# S7CAS-PLEIADES-CARTE-MERE_Pxx_ARBRE_CAP_.net
KiCad netlist of a schematic drawn in Altium Designer
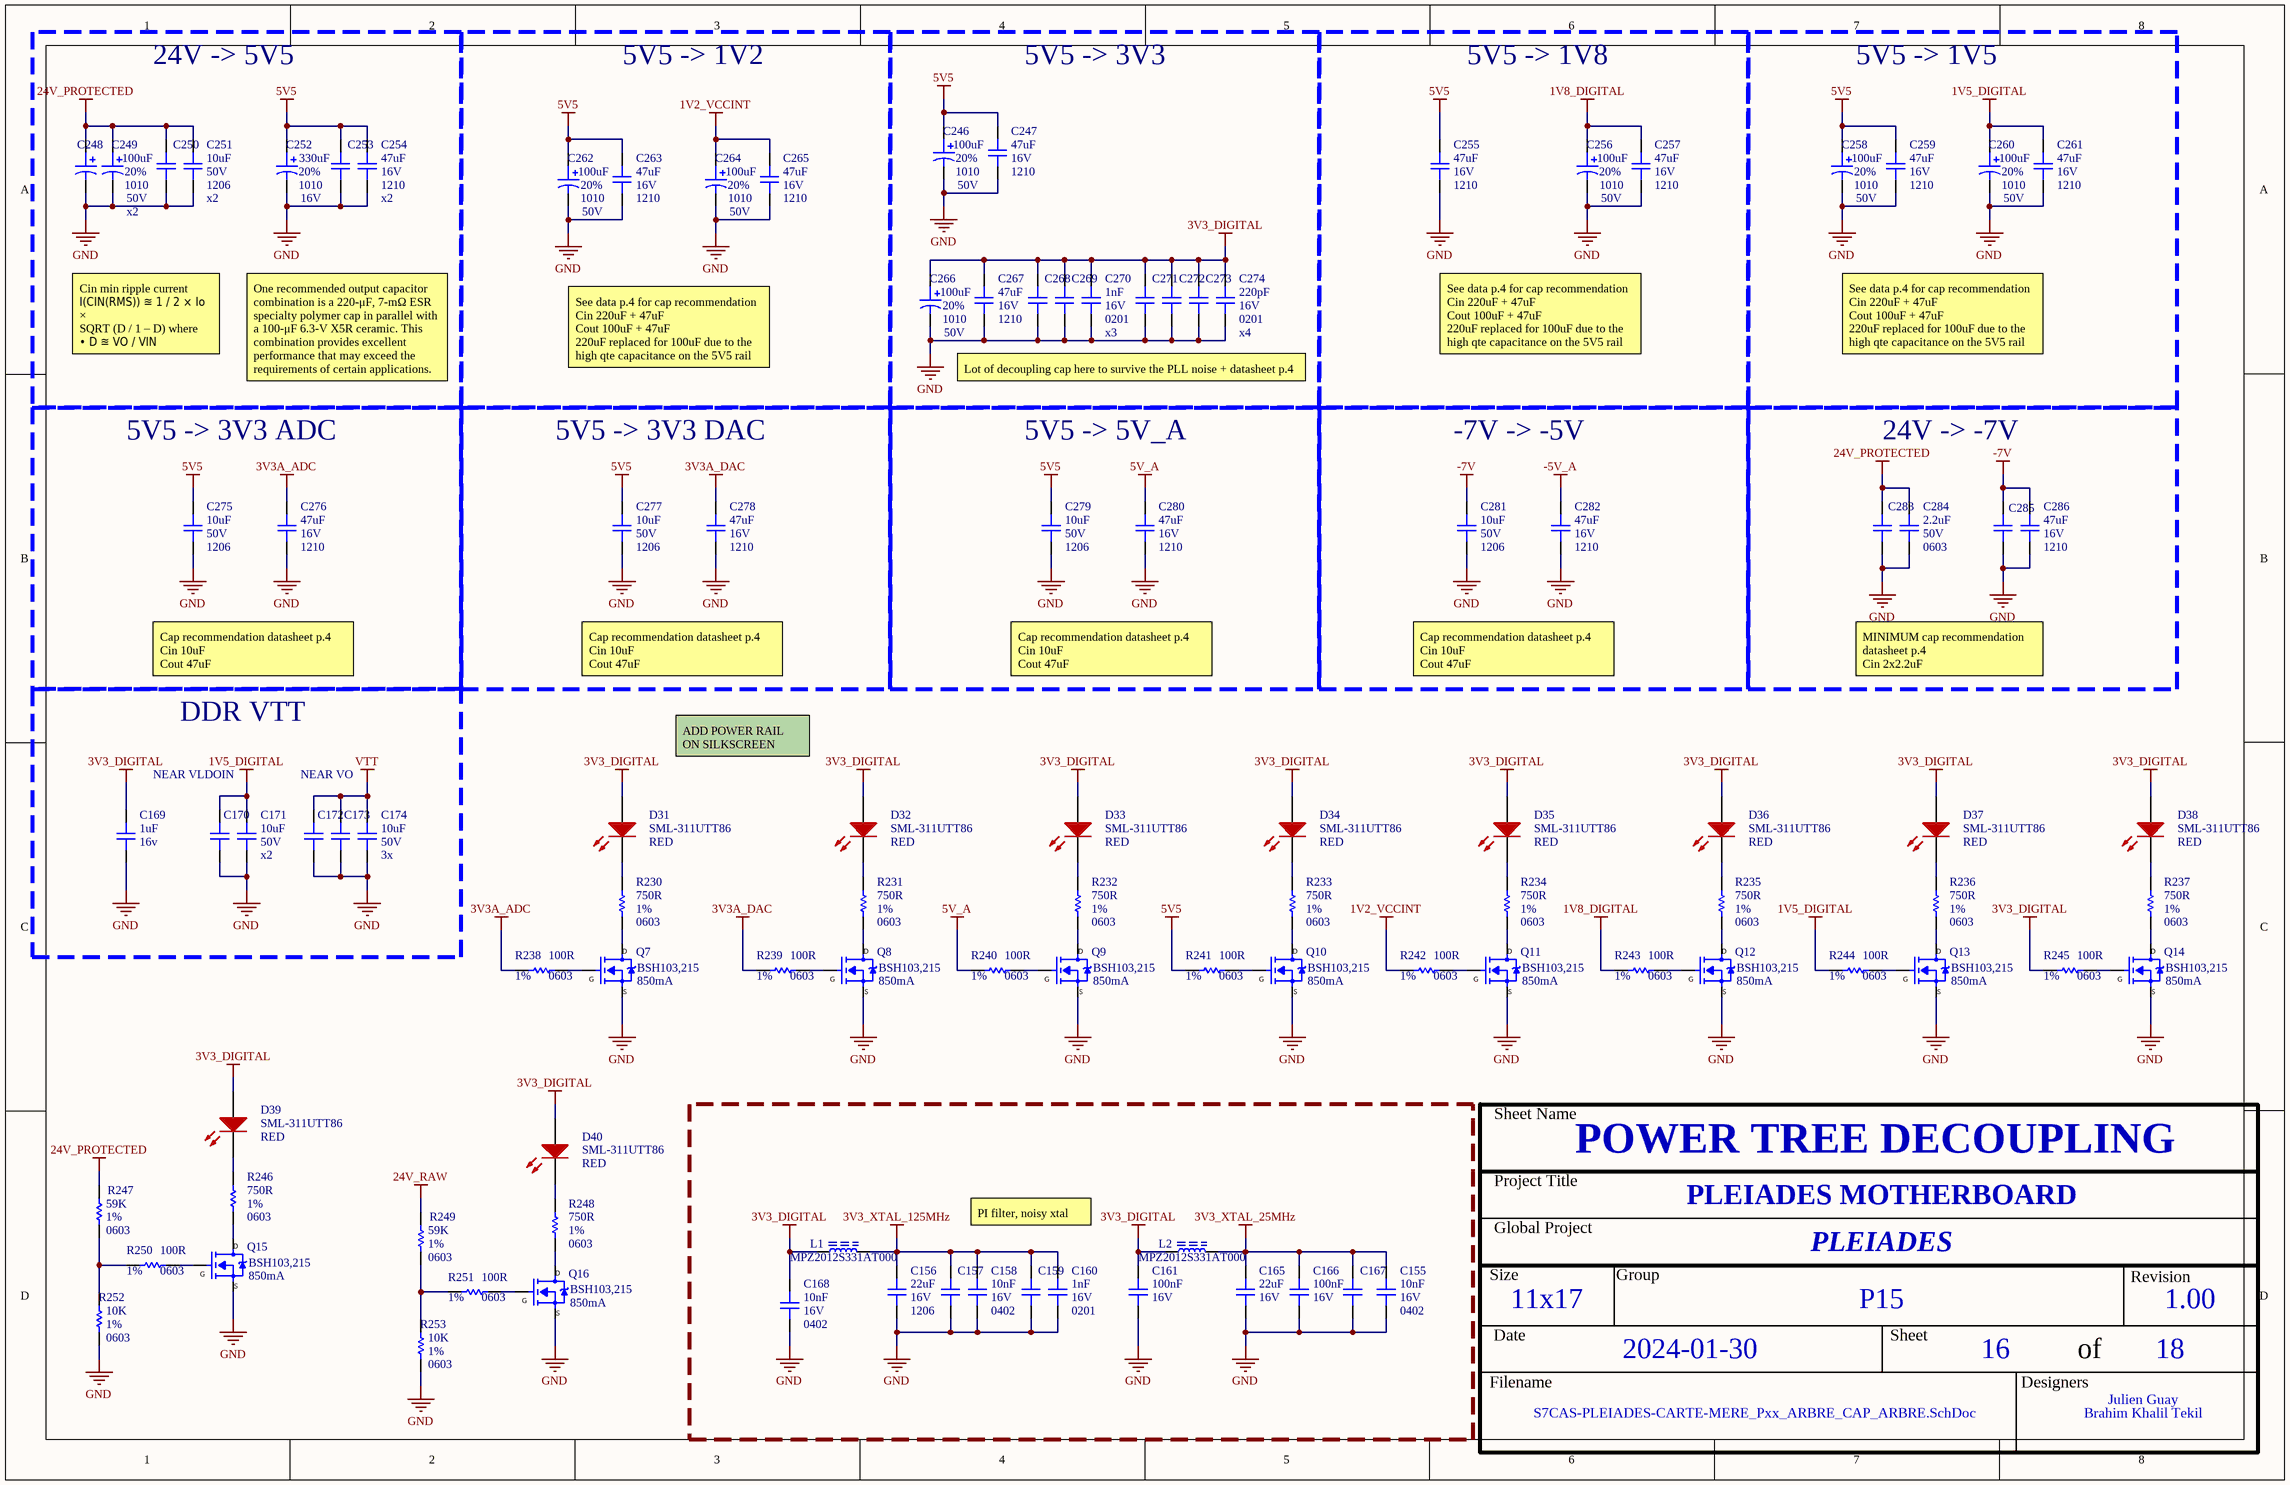
[diagram p0: S7CAS-PLEIADES-CARTE-MERE_Pxx_ARBRE_CAP_ARBRE.SchDoc]

(export (version "E")
  (design (tool "Eeschema 10.0.6"))
  (components
    (comp (ref "C155")
      (value "10nF")
      (footprint "CAP_0402")
      (description "CAP - 0402")
      (fields
        (field (name "VOLTAGE") "16V")
        (field (name "PACKAGE") "0402")
        (field (name "CREATEDBY") "Jonathan Bouchard")
      )
      (libsource (lib "S7CAS_LIB2023") (part "CAP - 0402"))
    )
    (comp (ref "C156")
      (value "22uF")
      (footprint "CAP_1206")
      (description "CAP - 1206")
      (fields
        (field (name "VOLTAGE") "16V")
        (field (name "PACKAGE") "1206")
        (field (name "CREATEDBY") "Jonathan Bouchard")
      )
      (libsource (lib "S7CAS_LIB2023") (part "CAP - 1206"))
    )
    (comp (ref "C157")
      (value "CAP - 0402")
      (footprint "CAP_0402")
      (fields (field (name "VOLTAGE") "16V") (field (name "CREATEDBY") "Jonathan Bouchard"))
      (libsource (lib "S7CAS_LIB2023") (part "CAP - 0402"))
    )
    (comp (ref "C158")
      (value "10nF")
      (footprint "CAP_0402")
      (description "CAP - 0402")
      (fields
        (field (name "VOLTAGE") "16V")
        (field (name "PACKAGE") "0402")
        (field (name "CREATEDBY") "Jonathan Bouchard")
      )
      (libsource (lib "S7CAS_LIB2023") (part "CAP - 0402"))
    )
    (comp (ref "C159")
      (value "CAP - 0201")
      (footprint "CAP_0201")
      (fields (field (name "VOLTAGE") "16V") (field (name "CREATEDBY") "Jonathan Bouchard"))
      (libsource (lib "S7CAS_LIB2023") (part "CAP - 0201"))
    )
    (comp (ref "C160")
      (value "1nF")
      (footprint "CAP_0201")
      (description "CAP - 0201")
      (fields
        (field (name "VOLTAGE") "16V")
        (field (name "PACKAGE") "0201")
        (field (name "CREATEDBY") "Jonathan Bouchard")
      )
      (libsource (lib "S7CAS_LIB2023") (part "CAP - 0201"))
    )
    (comp (ref "C161")
      (value "100nF")
      (footprint "CAP_0603")
      (description "CAP - 0603")
      (fields (field (name "VOLTAGE") "16V") (field (name "CREATEDBY") "Jonathan Bouchard"))
      (libsource (lib "S7CAS_LIB2023") (part "CAP - 0603"))
    )
    (comp (ref "C165")
      (value "22uF")
      (footprint "CAP_1206")
      (description "CAP - 1206")
      (fields (field (name "VOLTAGE") "16V") (field (name "CREATEDBY") "Jonathan Bouchard"))
      (libsource (lib "S7CAS_LIB2023") (part "CAP - 1206"))
    )
    (comp (ref "C166")
      (value "100nF")
      (footprint "CAP_0603")
      (description "CAP - 0603")
      (fields (field (name "VOLTAGE") "16V") (field (name "CREATEDBY") "Jonathan Bouchard"))
      (libsource (lib "S7CAS_LIB2023") (part "CAP - 0603"))
    )
    (comp (ref "C167")
      (value "CAP - 0402")
      (footprint "CAP_0402")
      (fields (field (name "VOLTAGE") "16V") (field (name "CREATEDBY") "Jonathan Bouchard"))
      (libsource (lib "S7CAS_LIB2023") (part "CAP - 0402"))
    )
    (comp (ref "C168")
      (value "10nF")
      (footprint "CAP_0402")
      (description "CAP - 0402")
      (fields
        (field (name "VOLTAGE") "16V")
        (field (name "PACKAGE") "0402")
        (field (name "CREATEDBY") "Jonathan Bouchard")
      )
      (libsource (lib "S7CAS_LIB2023") (part "CAP - 0402"))
    )
    (comp (ref "C169")
      (value "1uF")
      (footprint "CAP_0603")
      (description "CAP - 0603")
      (fields (field (name "VOLTAGE") "16v") (field (name "CREATEDBY") "Jonathan Bouchard"))
      (libsource (lib "S7CAS_LIB2023") (part "CAP - 0603"))
    )
    (comp (ref "C170")
      (value "CAP - 0805")
      (footprint "CAP_0805")
      (fields (field (name "VOLTAGE") "50V") (field (name "CREATEDBY") "Jonathan Bouchard"))
      (libsource (lib "S7CAS_LIB2023") (part "CAP - 0805"))
    )
    (comp (ref "C171")
      (value "10uF")
      (footprint "CAP_0805")
      (description "CAP - 0805")
      (fields (field (name "VOLTAGE") "50V") (field (name "CREATEDBY") "Jonathan Bouchard"))
      (libsource (lib "S7CAS_LIB2023") (part "CAP - 0805"))
    )
    (comp (ref "C172")
      (value "CAP - 0805")
      (footprint "CAP_0805")
      (fields (field (name "VOLTAGE") "50V") (field (name "CREATEDBY") "Jonathan Bouchard"))
      (libsource (lib "S7CAS_LIB2023") (part "CAP - 0805"))
    )
    (comp (ref "C173")
      (value "CAP - 0805")
      (footprint "CAP_0805")
      (fields (field (name "VOLTAGE") "50V") (field (name "CREATEDBY") "Jonathan Bouchard"))
      (libsource (lib "S7CAS_LIB2023") (part "CAP - 0805"))
    )
    (comp (ref "C174")
      (value "10uF")
      (footprint "CAP_0805")
      (description "CAP - 0805")
      (fields (field (name "VOLTAGE") "50V") (field (name "CREATEDBY") "Jonathan Bouchard"))
      (libsource (lib "S7CAS_LIB2023") (part "CAP - 0805"))
    )
    (comp (ref "C246")
      (value "100uF")
      (footprint "CAP_ALU_1010_vishay")
      (description "CAP - ALU 100uF 20% 50V - 1010")
      (fields
        (field (name "MFG") "Vishay Dale")
        (field (name "MFG PART NUMBER") "MAL215099101E3")
        (field (name "VOLTAGE") "50V")
        (field (name "PACKAGE") "1010")
        (field (name "PRECISION") "20%")
        (field (name "CREATEDBY") "Jonathan Bouchard")
      )
      (libsource (lib "S7CAS_LIB2023") (part "CAP_ALU_MAL215099101E3"))
    )
    (comp (ref "C247")
      (value "47uF")
      (footprint "CAP_1210")
      (description "CAP - 1210")
      (fields
        (field (name "VOLTAGE") "16V")
        (field (name "PACKAGE") "1210")
        (field (name "CREATEDBY") "Jonathan Bouchard")
      )
      (libsource (lib "S7CAS_LIB2023") (part "CAP - 1210"))
    )
    (comp (ref "C248")
      (value "MAL215099101E3")
      (footprint "CAP_ALU_1010_vishay")
      (description "CAP - ALU 100uF 20% 50V - 1010")
      (fields (field (name "MFG") "Vishay Dale") (field (name "CREATEDBY") "Jonathan Bouchard"))
      (libsource (lib "S7CAS_LIB2023") (part "CAP_ALU_MAL215099101E3"))
    )
    (comp (ref "C249")
      (value "100uF")
      (footprint "CAP_ALU_1010_vishay")
      (description "CAP - ALU 100uF 20% 50V - 1010")
      (fields
        (field (name "MFG") "Vishay Dale")
        (field (name "MFG PART NUMBER") "MAL215099101E3")
        (field (name "VOLTAGE") "50V")
        (field (name "PACKAGE") "1010")
        (field (name "PRECISION") "20%")
        (field (name "CREATEDBY") "Jonathan Bouchard")
      )
      (libsource (lib "S7CAS_LIB2023") (part "CAP_ALU_MAL215099101E3"))
    )
    (comp (ref "C250")
      (value "CAP - 1206")
      (footprint "CAP_1206")
      (fields (field (name "VOLTAGE") "50V") (field (name "CREATEDBY") "Jonathan Bouchard"))
      (libsource (lib "S7CAS_LIB2023") (part "CAP - 1206"))
    )
    (comp (ref "C251")
      (value "10uF")
      (footprint "CAP_1206")
      (description "CAP - 1206")
      (fields
        (field (name "VOLTAGE") "50V")
        (field (name "PACKAGE") "1206")
        (field (name "CREATEDBY") "Jonathan Bouchard")
      )
      (libsource (lib "S7CAS_LIB2023") (part "CAP - 1206"))
    )
    (comp (ref "C252")
      (value "330uF")
      (footprint "CAP_ALU_1010_vishay")
      (description "CAP - ALU 330uF 20% 16V - 1010")
      (fields
        (field (name "MFG") "Vishay Dale")
        (field (name "MFG PART NUMBER") "MAL214699501E3")
        (field (name "VOLTAGE") "16V")
        (field (name "PACKAGE") "1010")
        (field (name "PRECISION") "20%")
        (field (name "CREATEDBY") "Jonathan Bouchard")
      )
      (libsource (lib "S7CAS_LIB2023") (part "CAP_ALU_MAL214699501E3"))
    )
    (comp (ref "C253")
      (value "CAP - 1210")
      (footprint "CAP_1210")
      (fields (field (name "VOLTAGE") "16V") (field (name "CREATEDBY") "Jonathan Bouchard"))
      (libsource (lib "S7CAS_LIB2023") (part "CAP - 1210"))
    )
    (comp (ref "C254")
      (value "47uF")
      (footprint "CAP_1210")
      (description "CAP - 1210")
      (fields
        (field (name "VOLTAGE") "16V")
        (field (name "PACKAGE") "1210")
        (field (name "CREATEDBY") "Jonathan Bouchard")
      )
      (libsource (lib "S7CAS_LIB2023") (part "CAP - 1210"))
    )
    (comp (ref "C255")
      (value "47uF")
      (footprint "CAP_1210")
      (description "CAP - 1210")
      (fields
        (field (name "VOLTAGE") "16V")
        (field (name "PACKAGE") "1210")
        (field (name "CREATEDBY") "Jonathan Bouchard")
      )
      (libsource (lib "S7CAS_LIB2023") (part "CAP - 1210"))
    )
    (comp (ref "C256")
      (value "100uF")
      (footprint "CAP_ALU_1010_vishay")
      (description "CAP - ALU 100uF 20% 50V - 1010")
      (fields
        (field (name "MFG") "Vishay Dale")
        (field (name "MFG PART NUMBER") "MAL215099101E3")
        (field (name "VOLTAGE") "50V")
        (field (name "PACKAGE") "1010")
        (field (name "PRECISION") "20%")
        (field (name "CREATEDBY") "Jonathan Bouchard")
      )
      (libsource (lib "S7CAS_LIB2023") (part "CAP_ALU_MAL215099101E3"))
    )
    (comp (ref "C257")
      (value "47uF")
      (footprint "CAP_1210")
      (description "CAP - 1210")
      (fields
        (field (name "VOLTAGE") "16V")
        (field (name "PACKAGE") "1210")
        (field (name "CREATEDBY") "Jonathan Bouchard")
      )
      (libsource (lib "S7CAS_LIB2023") (part "CAP - 1210"))
    )
    (comp (ref "C258")
      (value "100uF")
      (footprint "CAP_ALU_1010_vishay")
      (description "CAP - ALU 100uF 20% 50V - 1010")
      (fields
        (field (name "MFG") "Vishay Dale")
        (field (name "MFG PART NUMBER") "MAL215099101E3")
        (field (name "VOLTAGE") "50V")
        (field (name "PACKAGE") "1010")
        (field (name "PRECISION") "20%")
        (field (name "CREATEDBY") "Jonathan Bouchard")
      )
      (libsource (lib "S7CAS_LIB2023") (part "CAP_ALU_MAL215099101E3"))
    )
    (comp (ref "C259")
      (value "47uF")
      (footprint "CAP_1210")
      (description "CAP - 1210")
      (fields
        (field (name "VOLTAGE") "16V")
        (field (name "PACKAGE") "1210")
        (field (name "CREATEDBY") "Jonathan Bouchard")
      )
      (libsource (lib "S7CAS_LIB2023") (part "CAP - 1210"))
    )
    (comp (ref "C260")
      (value "100uF")
      (footprint "CAP_ALU_1010_vishay")
      (description "CAP - ALU 100uF 20% 50V - 1010")
      (fields
        (field (name "MFG") "Vishay Dale")
        (field (name "MFG PART NUMBER") "MAL215099101E3")
        (field (name "VOLTAGE") "50V")
        (field (name "PACKAGE") "1010")
        (field (name "PRECISION") "20%")
        (field (name "CREATEDBY") "Jonathan Bouchard")
      )
      (libsource (lib "S7CAS_LIB2023") (part "CAP_ALU_MAL215099101E3"))
    )
    (comp (ref "C261")
      (value "47uF")
      (footprint "CAP_1210")
      (description "CAP - 1210")
      (fields
        (field (name "VOLTAGE") "16V")
        (field (name "PACKAGE") "1210")
        (field (name "CREATEDBY") "Jonathan Bouchard")
      )
      (libsource (lib "S7CAS_LIB2023") (part "CAP - 1210"))
    )
    (comp (ref "C262")
      (value "100uF")
      (footprint "CAP_ALU_1010_vishay")
      (description "CAP - ALU 100uF 20% 50V - 1010")
      (fields
        (field (name "MFG") "Vishay Dale")
        (field (name "MFG PART NUMBER") "MAL215099101E3")
        (field (name "VOLTAGE") "50V")
        (field (name "PACKAGE") "1010")
        (field (name "PRECISION") "20%")
        (field (name "CREATEDBY") "Jonathan Bouchard")
      )
      (libsource (lib "S7CAS_LIB2023") (part "CAP_ALU_MAL215099101E3"))
    )
    (comp (ref "C263")
      (value "47uF")
      (footprint "CAP_1210")
      (description "CAP - 1210")
      (fields
        (field (name "VOLTAGE") "16V")
        (field (name "PACKAGE") "1210")
        (field (name "CREATEDBY") "Jonathan Bouchard")
      )
      (libsource (lib "S7CAS_LIB2023") (part "CAP - 1210"))
    )
    (comp (ref "C264")
      (value "100uF")
      (footprint "CAP_ALU_1010_vishay")
      (description "CAP - ALU 100uF 20% 50V - 1010")
      (fields
        (field (name "MFG") "Vishay Dale")
        (field (name "MFG PART NUMBER") "MAL215099101E3")
        (field (name "VOLTAGE") "50V")
        (field (name "PACKAGE") "1010")
        (field (name "PRECISION") "20%")
        (field (name "CREATEDBY") "Jonathan Bouchard")
      )
      (libsource (lib "S7CAS_LIB2023") (part "CAP_ALU_MAL215099101E3"))
    )
    (comp (ref "C265")
      (value "47uF")
      (footprint "CAP_1210")
      (description "CAP - 1210")
      (fields
        (field (name "VOLTAGE") "16V")
        (field (name "PACKAGE") "1210")
        (field (name "CREATEDBY") "Jonathan Bouchard")
      )
      (libsource (lib "S7CAS_LIB2023") (part "CAP - 1210"))
    )
    (comp (ref "C266")
      (value "100uF")
      (footprint "CAP_ALU_1010_vishay")
      (description "CAP - ALU 100uF 20% 50V - 1010")
      (fields
        (field (name "MFG") "Vishay Dale")
        (field (name "MFG PART NUMBER") "MAL215099101E3")
        (field (name "VOLTAGE") "50V")
        (field (name "PACKAGE") "1010")
        (field (name "PRECISION") "20%")
        (field (name "CREATEDBY") "Jonathan Bouchard")
      )
      (libsource (lib "S7CAS_LIB2023") (part "CAP_ALU_MAL215099101E3"))
    )
    (comp (ref "C267")
      (value "47uF")
      (footprint "CAP_1210")
      (description "CAP - 1210")
      (fields
        (field (name "VOLTAGE") "16V")
        (field (name "PACKAGE") "1210")
        (field (name "CREATEDBY") "Jonathan Bouchard")
      )
      (libsource (lib "S7CAS_LIB2023") (part "CAP - 1210"))
    )
    (comp (ref "C268")
      (value "CAP - 0201")
      (footprint "CAP_0201")
      (fields (field (name "VOLTAGE") "16V") (field (name "CREATEDBY") "Jonathan Bouchard"))
      (libsource (lib "S7CAS_LIB2023") (part "CAP - 0201"))
    )
    (comp (ref "C269")
      (value "CAP - 0201")
      (footprint "CAP_0201")
      (fields (field (name "VOLTAGE") "16V") (field (name "CREATEDBY") "Jonathan Bouchard"))
      (libsource (lib "S7CAS_LIB2023") (part "CAP - 0201"))
    )
    (comp (ref "C270")
      (value "1nF")
      (footprint "CAP_0201")
      (description "CAP - 0201")
      (fields
        (field (name "VOLTAGE") "16V")
        (field (name "PACKAGE") "0201")
        (field (name "CREATEDBY") "Jonathan Bouchard")
      )
      (libsource (lib "S7CAS_LIB2023") (part "CAP - 0201"))
    )
    (comp (ref "C271")
      (value "CAP - 0201")
      (footprint "CAP_0201")
      (fields (field (name "VOLTAGE") "16V") (field (name "CREATEDBY") "Jonathan Bouchard"))
      (libsource (lib "S7CAS_LIB2023") (part "CAP - 0201"))
    )
    (comp (ref "C272")
      (value "CAP - 0201")
      (footprint "CAP_0201")
      (fields (field (name "VOLTAGE") "16V") (field (name "CREATEDBY") "Jonathan Bouchard"))
      (libsource (lib "S7CAS_LIB2023") (part "CAP - 0201"))
    )
    (comp (ref "C273")
      (value "CAP - 0201")
      (footprint "CAP_0201")
      (fields (field (name "VOLTAGE") "16V") (field (name "CREATEDBY") "Jonathan Bouchard"))
      (libsource (lib "S7CAS_LIB2023") (part "CAP - 0201"))
    )
    (comp (ref "C274")
      (value "220pF")
      (footprint "CAP_0201")
      (description "CAP - 0201")
      (fields
        (field (name "VOLTAGE") "16V")
        (field (name "PACKAGE") "0201")
        (field (name "CREATEDBY") "Jonathan Bouchard")
      )
      (libsource (lib "S7CAS_LIB2023") (part "CAP - 0201"))
    )
    (comp (ref "C275")
      (value "10uF")
      (footprint "CAP_1206")
      (description "CAP - 1206")
      (fields
        (field (name "VOLTAGE") "50V")
        (field (name "PACKAGE") "1206")
        (field (name "CREATEDBY") "Jonathan Bouchard")
      )
      (libsource (lib "S7CAS_LIB2023") (part "CAP - 1206"))
    )
    (comp (ref "C276")
      (value "47uF")
      (footprint "CAP_1210")
      (description "CAP - 1210")
      (fields
        (field (name "VOLTAGE") "16V")
        (field (name "PACKAGE") "1210")
        (field (name "CREATEDBY") "Jonathan Bouchard")
      )
      (libsource (lib "S7CAS_LIB2023") (part "CAP - 1210"))
    )
    (comp (ref "C277")
      (value "10uF")
      (footprint "CAP_1206")
      (description "CAP - 1206")
      (fields
        (field (name "VOLTAGE") "50V")
        (field (name "PACKAGE") "1206")
        (field (name "CREATEDBY") "Jonathan Bouchard")
      )
      (libsource (lib "S7CAS_LIB2023") (part "CAP - 1206"))
    )
    (comp (ref "C278")
      (value "47uF")
      (footprint "CAP_1210")
      (description "CAP - 1210")
      (fields
        (field (name "VOLTAGE") "16V")
        (field (name "PACKAGE") "1210")
        (field (name "CREATEDBY") "Jonathan Bouchard")
      )
      (libsource (lib "S7CAS_LIB2023") (part "CAP - 1210"))
    )
    (comp (ref "C279")
      (value "10uF")
      (footprint "CAP_1206")
      (description "CAP - 1206")
      (fields
        (field (name "VOLTAGE") "50V")
        (field (name "PACKAGE") "1206")
        (field (name "CREATEDBY") "Jonathan Bouchard")
      )
      (libsource (lib "S7CAS_LIB2023") (part "CAP - 1206"))
    )
    (comp (ref "C280")
      (value "47uF")
      (footprint "CAP_1210")
      (description "CAP - 1210")
      (fields
        (field (name "VOLTAGE") "16V")
        (field (name "PACKAGE") "1210")
        (field (name "CREATEDBY") "Jonathan Bouchard")
      )
      (libsource (lib "S7CAS_LIB2023") (part "CAP - 1210"))
    )
    (comp (ref "C281")
      (value "10uF")
      (footprint "CAP_1206")
      (description "CAP - 1206")
      (fields
        (field (name "VOLTAGE") "50V")
        (field (name "PACKAGE") "1206")
        (field (name "CREATEDBY") "Jonathan Bouchard")
      )
      (libsource (lib "S7CAS_LIB2023") (part "CAP - 1206"))
    )
    (comp (ref "C282")
      (value "47uF")
      (footprint "CAP_1210")
      (description "CAP - 1210")
      (fields
        (field (name "VOLTAGE") "16V")
        (field (name "PACKAGE") "1210")
        (field (name "CREATEDBY") "Jonathan Bouchard")
      )
      (libsource (lib "S7CAS_LIB2023") (part "CAP - 1210"))
    )
    (comp (ref "C283")
      (value "CAP - 0603")
      (footprint "CAP_0603")
      (fields (field (name "VOLTAGE") "50V") (field (name "CREATEDBY") "Jonathan Bouchard"))
      (libsource (lib "S7CAS_LIB2023") (part "CAP - 0603"))
    )
    (comp (ref "C284")
      (value "2.2uF")
      (footprint "CAP_0603")
      (description "CAP - 0603")
      (fields
        (field (name "VOLTAGE") "50V")
        (field (name "PACKAGE") "0603")
        (field (name "CREATEDBY") "Jonathan Bouchard")
      )
      (libsource (lib "S7CAS_LIB2023") (part "CAP - 0603"))
    )
    (comp (ref "C285")
      (value "CAP - 1210")
      (footprint "CAP_1210")
      (fields (field (name "VOLTAGE") "16V") (field (name "CREATEDBY") "Jonathan Bouchard"))
      (libsource (lib "S7CAS_LIB2023") (part "CAP - 1210"))
    )
    (comp (ref "C286")
      (value "47uF")
      (footprint "CAP_1210")
      (description "CAP - 1210")
      (fields
        (field (name "VOLTAGE") "16V")
        (field (name "PACKAGE") "1210")
        (field (name "CREATEDBY") "Jonathan Bouchard")
      )
      (libsource (lib "S7CAS_LIB2023") (part "CAP - 1210"))
    )
    (comp (ref "D31")
      (value "SML-311UTT86")
      (footprint "LED_0603")
      (description "LED - 620nM RED 2mA - 0603")
      (fields
        (field (name "VOLTAGE") "1.8V")
        (field (name "MFG") "ROHM Semiconductor")
        (field (name "ALTIUM_VALUE") "RED")
        (field (name "CREATEDBY") "Jonathan Bouchard")
      )
      (libsource (lib "S7CAS_LIB2023") (part "LED_SML-311UTT86"))
    )
    (comp (ref "D32")
      (value "SML-311UTT86")
      (footprint "LED_0603")
      (description "LED - 620nM RED 2mA - 0603")
      (fields
        (field (name "VOLTAGE") "1.8V")
        (field (name "MFG") "ROHM Semiconductor")
        (field (name "ALTIUM_VALUE") "RED")
        (field (name "CREATEDBY") "Jonathan Bouchard")
      )
      (libsource (lib "S7CAS_LIB2023") (part "LED_SML-311UTT86"))
    )
    (comp (ref "D33")
      (value "SML-311UTT86")
      (footprint "LED_0603")
      (description "LED - 620nM RED 2mA - 0603")
      (fields
        (field (name "VOLTAGE") "1.8V")
        (field (name "MFG") "ROHM Semiconductor")
        (field (name "ALTIUM_VALUE") "RED")
        (field (name "CREATEDBY") "Jonathan Bouchard")
      )
      (libsource (lib "S7CAS_LIB2023") (part "LED_SML-311UTT86"))
    )
    (comp (ref "D34")
      (value "SML-311UTT86")
      (footprint "LED_0603")
      (description "LED - 620nM RED 2mA - 0603")
      (fields
        (field (name "VOLTAGE") "1.8V")
        (field (name "MFG") "ROHM Semiconductor")
        (field (name "ALTIUM_VALUE") "RED")
        (field (name "CREATEDBY") "Jonathan Bouchard")
      )
      (libsource (lib "S7CAS_LIB2023") (part "LED_SML-311UTT86"))
    )
    (comp (ref "D35")
      (value "SML-311UTT86")
      (footprint "LED_0603")
      (description "LED - 620nM RED 2mA - 0603")
      (fields
        (field (name "VOLTAGE") "1.8V")
        (field (name "MFG") "ROHM Semiconductor")
        (field (name "ALTIUM_VALUE") "RED")
        (field (name "CREATEDBY") "Jonathan Bouchard")
      )
      (libsource (lib "S7CAS_LIB2023") (part "LED_SML-311UTT86"))
    )
    (comp (ref "D36")
      (value "SML-311UTT86")
      (footprint "LED_0603")
      (description "LED - 620nM RED 2mA - 0603")
      (fields
        (field (name "VOLTAGE") "1.8V")
        (field (name "MFG") "ROHM Semiconductor")
        (field (name "ALTIUM_VALUE") "RED")
        (field (name "CREATEDBY") "Jonathan Bouchard")
      )
      (libsource (lib "S7CAS_LIB2023") (part "LED_SML-311UTT86"))
    )
    (comp (ref "D37")
      (value "SML-311UTT86")
      (footprint "LED_0603")
      (description "LED - 620nM RED 2mA - 0603")
      (fields
        (field (name "VOLTAGE") "1.8V")
        (field (name "MFG") "ROHM Semiconductor")
        (field (name "ALTIUM_VALUE") "RED")
        (field (name "CREATEDBY") "Jonathan Bouchard")
      )
      (libsource (lib "S7CAS_LIB2023") (part "LED_SML-311UTT86"))
    )
    (comp (ref "D38")
      (value "SML-311UTT86")
      (footprint "LED_0603")
      (description "LED - 620nM RED 2mA - 0603")
      (fields
        (field (name "VOLTAGE") "1.8V")
        (field (name "MFG") "ROHM Semiconductor")
        (field (name "ALTIUM_VALUE") "RED")
        (field (name "CREATEDBY") "Jonathan Bouchard")
      )
      (libsource (lib "S7CAS_LIB2023") (part "LED_SML-311UTT86"))
    )
    (comp (ref "D39")
      (value "SML-311UTT86")
      (footprint "LED_0603")
      (description "LED - 620nM RED 2mA - 0603")
      (fields
        (field (name "VOLTAGE") "1.8V")
        (field (name "MFG") "ROHM Semiconductor")
        (field (name "ALTIUM_VALUE") "RED")
        (field (name "CREATEDBY") "Jonathan Bouchard")
      )
      (libsource (lib "S7CAS_LIB2023") (part "LED_SML-311UTT86"))
    )
    (comp (ref "D40")
      (value "SML-311UTT86")
      (footprint "LED_0603")
      (description "LED - 620nM RED 2mA - 0603")
      (fields
        (field (name "VOLTAGE") "1.8V")
        (field (name "MFG") "ROHM Semiconductor")
        (field (name "ALTIUM_VALUE") "RED")
        (field (name "CREATEDBY") "Jonathan Bouchard")
      )
      (libsource (lib "S7CAS_LIB2023") (part "LED_SML-311UTT86"))
    )
    (comp (ref "L1")
      (value "FER - 0805")
      (footprint "FER_0805")
      (fields
        (field (name "MFG") "TDK Corporation")
        (field (name "MFG PART NUMBER") "MPZ2012S331AT000")
        (field (name "CREATEDBY") "Jonathan Bouchard")
      )
      (libsource (lib "S7CAS_LIB2023") (part "FER - 0805"))
    )
    (comp (ref "L2")
      (value "FER - 0805")
      (footprint "FER_0805")
      (fields
        (field (name "MFG") "TDK Corporation")
        (field (name "MFG PART NUMBER") "MPZ2012S331AT000")
        (field (name "CREATEDBY") "Jonathan Bouchard")
      )
      (libsource (lib "S7CAS_LIB2023") (part "FER - 0805"))
    )
    (comp (ref "Q7")
      (value "BSH103,215")
      (footprint "SOT23-3")
      (description "N-Channel  Enhancement Mode Field Effect Transistor")
      (fields (field (name "CURRENT") "850mA"))
      (libsource (lib "S7CAS_LIB2023") (part "MOS_N_CHANNEL"))
    )
    (comp (ref "Q8")
      (value "BSH103,215")
      (footprint "SOT23-3")
      (description "N-Channel  Enhancement Mode Field Effect Transistor")
      (fields (field (name "CURRENT") "850mA"))
      (libsource (lib "S7CAS_LIB2023") (part "MOS_N_CHANNEL"))
    )
    (comp (ref "Q9")
      (value "BSH103,215")
      (footprint "SOT23-3")
      (description "N-Channel  Enhancement Mode Field Effect Transistor")
      (fields (field (name "CURRENT") "850mA"))
      (libsource (lib "S7CAS_LIB2023") (part "MOS_N_CHANNEL"))
    )
    (comp (ref "Q10")
      (value "BSH103,215")
      (footprint "SOT23-3")
      (description "N-Channel  Enhancement Mode Field Effect Transistor")
      (fields (field (name "CURRENT") "850mA"))
      (libsource (lib "S7CAS_LIB2023") (part "MOS_N_CHANNEL"))
    )
    (comp (ref "Q11")
      (value "BSH103,215")
      (footprint "SOT23-3")
      (description "N-Channel  Enhancement Mode Field Effect Transistor")
      (fields (field (name "CURRENT") "850mA"))
      (libsource (lib "S7CAS_LIB2023") (part "MOS_N_CHANNEL"))
    )
    (comp (ref "Q12")
      (value "BSH103,215")
      (footprint "SOT23-3")
      (description "N-Channel  Enhancement Mode Field Effect Transistor")
      (fields (field (name "CURRENT") "850mA"))
      (libsource (lib "S7CAS_LIB2023") (part "MOS_N_CHANNEL"))
    )
    (comp (ref "Q13")
      (value "BSH103,215")
      (footprint "SOT23-3")
      (description "N-Channel  Enhancement Mode Field Effect Transistor")
      (fields (field (name "CURRENT") "850mA"))
      (libsource (lib "S7CAS_LIB2023") (part "MOS_N_CHANNEL"))
    )
    (comp (ref "Q14")
      (value "BSH103,215")
      (footprint "SOT23-3")
      (description "N-Channel  Enhancement Mode Field Effect Transistor")
      (fields (field (name "CURRENT") "850mA"))
      (libsource (lib "S7CAS_LIB2023") (part "MOS_N_CHANNEL"))
    )
    (comp (ref "Q15")
      (value "BSH103,215")
      (footprint "SOT23-3")
      (description "N-Channel  Enhancement Mode Field Effect Transistor")
      (fields (field (name "CURRENT") "850mA"))
      (libsource (lib "S7CAS_LIB2023") (part "MOS_N_CHANNEL"))
    )
    (comp (ref "Q16")
      (value "BSH103,215")
      (footprint "SOT23-3")
      (description "N-Channel  Enhancement Mode Field Effect Transistor")
      (fields (field (name "CURRENT") "850mA"))
      (libsource (lib "S7CAS_LIB2023") (part "MOS_N_CHANNEL"))
    )
    (comp (ref "R230")
      (value "750R")
      (footprint "RES_0603")
      (description "RES - 0603")
      (fields
        (field (name "PACKAGE") "0603")
        (field (name "PRECISION") "1%")
        (field (name "CREATEDBY") "Jonathan Bouchard")
      )
      (libsource (lib "S7CAS_LIB2023") (part "RES - 0603"))
    )
    (comp (ref "R231")
      (value "750R")
      (footprint "RES_0603")
      (description "RES - 0603")
      (fields
        (field (name "PACKAGE") "0603")
        (field (name "PRECISION") "1%")
        (field (name "CREATEDBY") "Jonathan Bouchard")
      )
      (libsource (lib "S7CAS_LIB2023") (part "RES - 0603"))
    )
    (comp (ref "R232")
      (value "750R")
      (footprint "RES_0603")
      (description "RES - 0603")
      (fields
        (field (name "PACKAGE") "0603")
        (field (name "PRECISION") "1%")
        (field (name "CREATEDBY") "Jonathan Bouchard")
      )
      (libsource (lib "S7CAS_LIB2023") (part "RES - 0603"))
    )
    (comp (ref "R233")
      (value "750R")
      (footprint "RES_0603")
      (description "RES - 0603")
      (fields
        (field (name "PACKAGE") "0603")
        (field (name "PRECISION") "1%")
        (field (name "CREATEDBY") "Jonathan Bouchard")
      )
      (libsource (lib "S7CAS_LIB2023") (part "RES - 0603"))
    )
    (comp (ref "R234")
      (value "750R")
      (footprint "RES_0603")
      (description "RES - 0603")
      (fields
        (field (name "PACKAGE") "0603")
        (field (name "PRECISION") "1%")
        (field (name "CREATEDBY") "Jonathan Bouchard")
      )
      (libsource (lib "S7CAS_LIB2023") (part "RES - 0603"))
    )
    (comp (ref "R235")
      (value "750R")
      (footprint "RES_0603")
      (description "RES - 0603")
      (fields
        (field (name "PACKAGE") "0603")
        (field (name "PRECISION") "1%")
        (field (name "CREATEDBY") "Jonathan Bouchard")
      )
      (libsource (lib "S7CAS_LIB2023") (part "RES - 0603"))
    )
    (comp (ref "R236")
      (value "750R")
      (footprint "RES_0603")
      (description "RES - 0603")
      (fields
        (field (name "PACKAGE") "0603")
        (field (name "PRECISION") "1%")
        (field (name "CREATEDBY") "Jonathan Bouchard")
      )
      (libsource (lib "S7CAS_LIB2023") (part "RES - 0603"))
    )
    (comp (ref "R237")
      (value "750R")
      (footprint "RES_0603")
      (description "RES - 0603")
      (fields
        (field (name "PACKAGE") "0603")
        (field (name "PRECISION") "1%")
        (field (name "CREATEDBY") "Jonathan Bouchard")
      )
      (libsource (lib "S7CAS_LIB2023") (part "RES - 0603"))
    )
    (comp (ref "R238")
      (value "100R")
      (footprint "RES_0603")
      (description "RES - 0603")
      (fields
        (field (name "PACKAGE") "0603")
        (field (name "PRECISION") "1%")
        (field (name "CREATEDBY") "Jonathan Bouchard")
      )
      (libsource (lib "S7CAS_LIB2023") (part "RES - 0603"))
    )
    (comp (ref "R239")
      (value "100R")
      (footprint "RES_0603")
      (description "RES - 0603")
      (fields
        (field (name "PACKAGE") "0603")
        (field (name "PRECISION") "1%")
        (field (name "CREATEDBY") "Jonathan Bouchard")
      )
      (libsource (lib "S7CAS_LIB2023") (part "RES - 0603"))
    )
    (comp (ref "R240")
      (value "100R")
      (footprint "RES_0603")
      (description "RES - 0603")
      (fields
        (field (name "PACKAGE") "0603")
        (field (name "PRECISION") "1%")
        (field (name "CREATEDBY") "Jonathan Bouchard")
      )
      (libsource (lib "S7CAS_LIB2023") (part "RES - 0603"))
    )
    (comp (ref "R241")
      (value "100R")
      (footprint "RES_0603")
      (description "RES - 0603")
      (fields
        (field (name "PACKAGE") "0603")
        (field (name "PRECISION") "1%")
        (field (name "CREATEDBY") "Jonathan Bouchard")
      )
      (libsource (lib "S7CAS_LIB2023") (part "RES - 0603"))
    )
    (comp (ref "R242")
      (value "100R")
      (footprint "RES_0603")
      (description "RES - 0603")
      (fields
        (field (name "PACKAGE") "0603")
        (field (name "PRECISION") "1%")
        (field (name "CREATEDBY") "Jonathan Bouchard")
      )
      (libsource (lib "S7CAS_LIB2023") (part "RES - 0603"))
    )
    (comp (ref "R243")
      (value "100R")
      (footprint "RES_0603")
      (description "RES - 0603")
      (fields
        (field (name "PACKAGE") "0603")
        (field (name "PRECISION") "1%")
        (field (name "CREATEDBY") "Jonathan Bouchard")
      )
      (libsource (lib "S7CAS_LIB2023") (part "RES - 0603"))
    )
    (comp (ref "R244")
      (value "100R")
      (footprint "RES_0603")
      (description "RES - 0603")
      (fields
        (field (name "PACKAGE") "0603")
        (field (name "PRECISION") "1%")
        (field (name "CREATEDBY") "Jonathan Bouchard")
      )
      (libsource (lib "S7CAS_LIB2023") (part "RES - 0603"))
    )
    (comp (ref "R245")
      (value "100R")
      (footprint "RES_0603")
      (description "RES - 0603")
      (fields
        (field (name "PACKAGE") "0603")
        (field (name "PRECISION") "1%")
        (field (name "CREATEDBY") "Jonathan Bouchard")
      )
      (libsource (lib "S7CAS_LIB2023") (part "RES - 0603"))
    )
    (comp (ref "R246")
      (value "750R")
      (footprint "RES_0603")
      (description "RES - 0603")
      (fields
        (field (name "PACKAGE") "0603")
        (field (name "PRECISION") "1%")
        (field (name "CREATEDBY") "Jonathan Bouchard")
      )
      (libsource (lib "S7CAS_LIB2023") (part "RES - 0603"))
    )
    (comp (ref "R247")
      (value "59K")
      (footprint "RES_0603")
      (description "RES - 0603")
      (fields
        (field (name "PACKAGE") "0603")
        (field (name "PRECISION") "1%")
        (field (name "CREATEDBY") "Jonathan Bouchard")
      )
      (libsource (lib "S7CAS_LIB2023") (part "RES - 0603"))
    )
    (comp (ref "R248")
      (value "750R")
      (footprint "RES_0603")
      (description "RES - 0603")
      (fields
        (field (name "PACKAGE") "0603")
        (field (name "PRECISION") "1%")
        (field (name "CREATEDBY") "Jonathan Bouchard")
      )
      (libsource (lib "S7CAS_LIB2023") (part "RES - 0603"))
    )
    (comp (ref "R249")
      (value "59K")
      (footprint "RES_0603")
      (description "RES - 0603")
      (fields
        (field (name "PACKAGE") "0603")
        (field (name "PRECISION") "1%")
        (field (name "CREATEDBY") "Jonathan Bouchard")
      )
      (libsource (lib "S7CAS_LIB2023") (part "RES - 0603"))
    )
    (comp (ref "R250")
      (value "100R")
      (footprint "RES_0603")
      (description "RES - 0603")
      (fields
        (field (name "PACKAGE") "0603")
        (field (name "PRECISION") "1%")
        (field (name "CREATEDBY") "Jonathan Bouchard")
      )
      (libsource (lib "S7CAS_LIB2023") (part "RES - 0603"))
    )
    (comp (ref "R251")
      (value "100R")
      (footprint "RES_0603")
      (description "RES - 0603")
      (fields
        (field (name "PACKAGE") "0603")
        (field (name "PRECISION") "1%")
        (field (name "CREATEDBY") "Jonathan Bouchard")
      )
      (libsource (lib "S7CAS_LIB2023") (part "RES - 0603"))
    )
    (comp (ref "R252")
      (value "10K")
      (footprint "RES_0603")
      (description "RES - 0603")
      (fields
        (field (name "PACKAGE") "0603")
        (field (name "PRECISION") "1%")
        (field (name "CREATEDBY") "Jonathan Bouchard")
      )
      (libsource (lib "S7CAS_LIB2023") (part "RES - 0603"))
    )
    (comp (ref "R253")
      (value "10K")
      (footprint "RES_0603")
      (description "RES - 0603")
      (fields
        (field (name "PACKAGE") "0603")
        (field (name "PRECISION") "1%")
        (field (name "CREATEDBY") "Jonathan Bouchard")
      )
      (libsource (lib "S7CAS_LIB2023") (part "RES - 0603"))
    )
  )
  (nets
    (net (code "1") (name "-5V_A") (class "Default")
      (node (ref "C282") (pin "2") (pinfunction "2_2") (pintype "passive"))
    )
    (net (code "2") (name "-7V") (class "Default")
      (node (ref "C281") (pin "2") (pinfunction "2_2") (pintype "passive"))
      (node (ref "C285") (pin "2") (pinfunction "2_2") (pintype "passive"))
      (node (ref "C286") (pin "2") (pinfunction "2_2") (pintype "passive"))
    )
    (net (code "3") (name "1V2_VCCINT") (class "Default")
      (node (ref "C264") (pin "1") (pinfunction "1_1") (pintype "passive"))
      (node (ref "C265") (pin "2") (pinfunction "2_2") (pintype "passive"))
      (node (ref "R242") (pin "2") (pinfunction "2_2") (pintype "passive"))
    )
    (net (code "4") (name "1V5_DIGITAL") (class "Default")
      (node (ref "C170") (pin "2") (pinfunction "2_2") (pintype "passive"))
      (node (ref "C171") (pin "2") (pinfunction "2_2") (pintype "passive"))
      (node (ref "C260") (pin "1") (pinfunction "1_1") (pintype "passive"))
      (node (ref "C261") (pin "2") (pinfunction "2_2") (pintype "passive"))
      (node (ref "R244") (pin "2") (pinfunction "2_2") (pintype "passive"))
    )
    (net (code "5") (name "1V8_DIGITAL") (class "Default")
      (node (ref "C256") (pin "1") (pinfunction "1_1") (pintype "passive"))
      (node (ref "C257") (pin "2") (pinfunction "2_2") (pintype "passive"))
      (node (ref "R243") (pin "2") (pinfunction "2_2") (pintype "passive"))
    )
    (net (code "6") (name "3V3A_ADC") (class "Default")
      (node (ref "C276") (pin "2") (pinfunction "2_2") (pintype "passive"))
      (node (ref "R238") (pin "2") (pinfunction "2_2") (pintype "passive"))
    )
    (net (code "7") (name "3V3A_DAC") (class "Default")
      (node (ref "C278") (pin "2") (pinfunction "2_2") (pintype "passive"))
      (node (ref "R239") (pin "2") (pinfunction "2_2") (pintype "passive"))
    )
    (net (code "8") (name "3V3_DIGITAL") (class "Default")
      (node (ref "C161") (pin "2") (pinfunction "2_2") (pintype "passive"))
      (node (ref "C168") (pin "2") (pinfunction "2_2") (pintype "passive"))
      (node (ref "C169") (pin "2") (pinfunction "2_2") (pintype "passive"))
      (node (ref "C266") (pin "1") (pinfunction "1_1") (pintype "passive"))
      (node (ref "C267") (pin "2") (pinfunction "2_2") (pintype "passive"))
      (node (ref "C268") (pin "2") (pinfunction "2_2") (pintype "passive"))
      (node (ref "C269") (pin "2") (pinfunction "2_2") (pintype "passive"))
      (node (ref "C270") (pin "2") (pinfunction "2_2") (pintype "passive"))
      (node (ref "C271") (pin "2") (pinfunction "2_2") (pintype "passive"))
      (node (ref "C272") (pin "2") (pinfunction "2_2") (pintype "passive"))
      (node (ref "C273") (pin "2") (pinfunction "2_2") (pintype "passive"))
      (node (ref "C274") (pin "2") (pinfunction "2_2") (pintype "passive"))
      (node (ref "D31") (pin "A") (pinfunction "A_A") (pintype "passive"))
      (node (ref "D32") (pin "A") (pinfunction "A_A") (pintype "passive"))
      (node (ref "D33") (pin "A") (pinfunction "A_A") (pintype "passive"))
      (node (ref "D34") (pin "A") (pinfunction "A_A") (pintype "passive"))
      (node (ref "D35") (pin "A") (pinfunction "A_A") (pintype "passive"))
      (node (ref "D36") (pin "A") (pinfunction "A_A") (pintype "passive"))
      (node (ref "D37") (pin "A") (pinfunction "A_A") (pintype "passive"))
      (node (ref "D38") (pin "A") (pinfunction "A_A") (pintype "passive"))
      (node (ref "D39") (pin "A") (pinfunction "A_A") (pintype "passive"))
      (node (ref "D40") (pin "A") (pinfunction "A_A") (pintype "passive"))
      (node (ref "L1") (pin "2") (pinfunction "2_2") (pintype "passive"))
      (node (ref "L2") (pin "2") (pinfunction "2_2") (pintype "passive"))
      (node (ref "R245") (pin "2") (pinfunction "2_2") (pintype "passive"))
    )
    (net (code "9") (name "3V3_XTAL_25MHz") (class "Default")
      (node (ref "C155") (pin "2") (pinfunction "2_2") (pintype "passive"))
      (node (ref "C165") (pin "2") (pinfunction "2_2") (pintype "passive"))
      (node (ref "C166") (pin "2") (pinfunction "2_2") (pintype "passive"))
      (node (ref "C167") (pin "2") (pinfunction "2_2") (pintype "passive"))
      (node (ref "L2") (pin "1") (pinfunction "1_1") (pintype "passive"))
    )
    (net (code "10") (name "3V3_XTAL_125MHz") (class "Default")
      (node (ref "C156") (pin "2") (pinfunction "2_2") (pintype "passive"))
      (node (ref "C157") (pin "2") (pinfunction "2_2") (pintype "passive"))
      (node (ref "C158") (pin "2") (pinfunction "2_2") (pintype "passive"))
      (node (ref "C159") (pin "2") (pinfunction "2_2") (pintype "passive"))
      (node (ref "C160") (pin "2") (pinfunction "2_2") (pintype "passive"))
      (node (ref "L1") (pin "1") (pinfunction "1_1") (pintype "passive"))
    )
    (net (code "11") (name "5V5") (class "Default")
      (node (ref "C246") (pin "1") (pinfunction "1_1") (pintype "passive"))
      (node (ref "C247") (pin "2") (pinfunction "2_2") (pintype "passive"))
      (node (ref "C252") (pin "1") (pinfunction "1_1") (pintype "passive"))
      (node (ref "C253") (pin "2") (pinfunction "2_2") (pintype "passive"))
      (node (ref "C254") (pin "2") (pinfunction "2_2") (pintype "passive"))
      (node (ref "C255") (pin "2") (pinfunction "2_2") (pintype "passive"))
      (node (ref "C258") (pin "1") (pinfunction "1_1") (pintype "passive"))
      (node (ref "C259") (pin "2") (pinfunction "2_2") (pintype "passive"))
      (node (ref "C262") (pin "1") (pinfunction "1_1") (pintype "passive"))
      (node (ref "C263") (pin "2") (pinfunction "2_2") (pintype "passive"))
      (node (ref "C275") (pin "2") (pinfunction "2_2") (pintype "passive"))
      (node (ref "C277") (pin "2") (pinfunction "2_2") (pintype "passive"))
      (node (ref "C279") (pin "2") (pinfunction "2_2") (pintype "passive"))
      (node (ref "R241") (pin "2") (pinfunction "2_2") (pintype "passive"))
    )
    (net (code "12") (name "5V_A") (class "Default")
      (node (ref "C280") (pin "2") (pinfunction "2_2") (pintype "passive"))
      (node (ref "R240") (pin "2") (pinfunction "2_2") (pintype "passive"))
    )
    (net (code "13") (name "24V_PROTECTED") (class "Default")
      (node (ref "C248") (pin "1") (pinfunction "1_1") (pintype "passive"))
      (node (ref "C249") (pin "1") (pinfunction "1_1") (pintype "passive"))
      (node (ref "C250") (pin "2") (pinfunction "2_2") (pintype "passive"))
      (node (ref "C251") (pin "2") (pinfunction "2_2") (pintype "passive"))
      (node (ref "C283") (pin "2") (pinfunction "2_2") (pintype "passive"))
      (node (ref "C284") (pin "2") (pinfunction "2_2") (pintype "passive"))
      (node (ref "R247") (pin "2") (pinfunction "2_2") (pintype "passive"))
    )
    (net (code "14") (name "24V_RAW") (class "Default")
      (node (ref "R249") (pin "2") (pinfunction "2_2") (pintype "passive"))
    )
    (net (code "15") (name "GND") (class "Default")
      (node (ref "C155") (pin "1") (pinfunction "1_1") (pintype "passive"))
      (node (ref "C156") (pin "1") (pinfunction "1_1") (pintype "passive"))
      (node (ref "C157") (pin "1") (pinfunction "1_1") (pintype "passive"))
      (node (ref "C158") (pin "1") (pinfunction "1_1") (pintype "passive"))
      (node (ref "C159") (pin "1") (pinfunction "1_1") (pintype "passive"))
      (node (ref "C160") (pin "1") (pinfunction "1_1") (pintype "passive"))
      (node (ref "C161") (pin "1") (pinfunction "1_1") (pintype "passive"))
      (node (ref "C165") (pin "1") (pinfunction "1_1") (pintype "passive"))
      (node (ref "C166") (pin "1") (pinfunction "1_1") (pintype "passive"))
      (node (ref "C167") (pin "1") (pinfunction "1_1") (pintype "passive"))
      (node (ref "C168") (pin "1") (pinfunction "1_1") (pintype "passive"))
      (node (ref "C169") (pin "1") (pinfunction "1_1") (pintype "passive"))
      (node (ref "C170") (pin "1") (pinfunction "1_1") (pintype "passive"))
      (node (ref "C171") (pin "1") (pinfunction "1_1") (pintype "passive"))
      (node (ref "C172") (pin "1") (pinfunction "1_1") (pintype "passive"))
      (node (ref "C173") (pin "1") (pinfunction "1_1") (pintype "passive"))
      (node (ref "C174") (pin "1") (pinfunction "1_1") (pintype "passive"))
      (node (ref "C246") (pin "2") (pinfunction "2_2") (pintype "passive"))
      (node (ref "C247") (pin "1") (pinfunction "1_1") (pintype "passive"))
      (node (ref "C248") (pin "2") (pinfunction "2_2") (pintype "passive"))
      (node (ref "C249") (pin "2") (pinfunction "2_2") (pintype "passive"))
      (node (ref "C250") (pin "1") (pinfunction "1_1") (pintype "passive"))
      (node (ref "C251") (pin "1") (pinfunction "1_1") (pintype "passive"))
      (node (ref "C252") (pin "2") (pinfunction "2_2") (pintype "passive"))
      (node (ref "C253") (pin "1") (pinfunction "1_1") (pintype "passive"))
      (node (ref "C254") (pin "1") (pinfunction "1_1") (pintype "passive"))
      (node (ref "C255") (pin "1") (pinfunction "1_1") (pintype "passive"))
      (node (ref "C256") (pin "2") (pinfunction "2_2") (pintype "passive"))
      (node (ref "C257") (pin "1") (pinfunction "1_1") (pintype "passive"))
      (node (ref "C258") (pin "2") (pinfunction "2_2") (pintype "passive"))
      (node (ref "C259") (pin "1") (pinfunction "1_1") (pintype "passive"))
      (node (ref "C260") (pin "2") (pinfunction "2_2") (pintype "passive"))
      (node (ref "C261") (pin "1") (pinfunction "1_1") (pintype "passive"))
      (node (ref "C262") (pin "2") (pinfunction "2_2") (pintype "passive"))
      (node (ref "C263") (pin "1") (pinfunction "1_1") (pintype "passive"))
      (node (ref "C264") (pin "2") (pinfunction "2_2") (pintype "passive"))
      (node (ref "C265") (pin "1") (pinfunction "1_1") (pintype "passive"))
      (node (ref "C266") (pin "2") (pinfunction "2_2") (pintype "passive"))
      (node (ref "C267") (pin "1") (pinfunction "1_1") (pintype "passive"))
      (node (ref "C268") (pin "1") (pinfunction "1_1") (pintype "passive"))
      (node (ref "C269") (pin "1") (pinfunction "1_1") (pintype "passive"))
      (node (ref "C270") (pin "1") (pinfunction "1_1") (pintype "passive"))
      (node (ref "C271") (pin "1") (pinfunction "1_1") (pintype "passive"))
      (node (ref "C272") (pin "1") (pinfunction "1_1") (pintype "passive"))
      (node (ref "C273") (pin "1") (pinfunction "1_1") (pintype "passive"))
      (node (ref "C274") (pin "1") (pinfunction "1_1") (pintype "passive"))
      (node (ref "C275") (pin "1") (pinfunction "1_1") (pintype "passive"))
      (node (ref "C276") (pin "1") (pinfunction "1_1") (pintype "passive"))
      (node (ref "C277") (pin "1") (pinfunction "1_1") (pintype "passive"))
      (node (ref "C278") (pin "1") (pinfunction "1_1") (pintype "passive"))
      (node (ref "C279") (pin "1") (pinfunction "1_1") (pintype "passive"))
      (node (ref "C280") (pin "1") (pinfunction "1_1") (pintype "passive"))
      (node (ref "C281") (pin "1") (pinfunction "1_1") (pintype "passive"))
      (node (ref "C282") (pin "1") (pinfunction "1_1") (pintype "passive"))
      (node (ref "C283") (pin "1") (pinfunction "1_1") (pintype "passive"))
      (node (ref "C284") (pin "1") (pinfunction "1_1") (pintype "passive"))
      (node (ref "C285") (pin "1") (pinfunction "1_1") (pintype "passive"))
      (node (ref "C286") (pin "1") (pinfunction "1_1") (pintype "passive"))
      (node (ref "Q10") (pin "2") (pintype "passive"))
      (node (ref "Q11") (pin "2") (pintype "passive"))
      (node (ref "Q12") (pin "2") (pintype "passive"))
      (node (ref "Q13") (pin "2") (pintype "passive"))
      (node (ref "Q14") (pin "2") (pintype "passive"))
      (node (ref "Q15") (pin "2") (pintype "passive"))
      (node (ref "Q16") (pin "2") (pintype "passive"))
      (node (ref "Q7") (pin "2") (pintype "passive"))
      (node (ref "Q8") (pin "2") (pintype "passive"))
      (node (ref "Q9") (pin "2") (pintype "passive"))
      (node (ref "R252") (pin "1") (pinfunction "1_1") (pintype "passive"))
      (node (ref "R253") (pin "1") (pinfunction "1_1") (pintype "passive"))
    )
    (net (code "16") (name "Net-(D31-PadK)") (class "Default")
      (node (ref "D31") (pin "K") (pinfunction "K_K") (pintype "passive"))
      (node (ref "R230") (pin "2") (pinfunction "2_2") (pintype "passive"))
    )
    (net (code "17") (name "Net-(D32-PadK)") (class "Default")
      (node (ref "D32") (pin "K") (pinfunction "K_K") (pintype "passive"))
      (node (ref "R231") (pin "2") (pinfunction "2_2") (pintype "passive"))
    )
    (net (code "18") (name "Net-(D33-PadK)") (class "Default")
      (node (ref "D33") (pin "K") (pinfunction "K_K") (pintype "passive"))
      (node (ref "R232") (pin "2") (pinfunction "2_2") (pintype "passive"))
    )
    (net (code "19") (name "Net-(D34-PadK)") (class "Default")
      (node (ref "D34") (pin "K") (pinfunction "K_K") (pintype "passive"))
      (node (ref "R233") (pin "2") (pinfunction "2_2") (pintype "passive"))
    )
    (net (code "20") (name "Net-(D35-PadK)") (class "Default")
      (node (ref "D35") (pin "K") (pinfunction "K_K") (pintype "passive"))
      (node (ref "R234") (pin "2") (pinfunction "2_2") (pintype "passive"))
    )
    (net (code "21") (name "Net-(D36-PadK)") (class "Default")
      (node (ref "D36") (pin "K") (pinfunction "K_K") (pintype "passive"))
      (node (ref "R235") (pin "2") (pinfunction "2_2") (pintype "passive"))
    )
    (net (code "22") (name "Net-(D37-PadK)") (class "Default")
      (node (ref "D37") (pin "K") (pinfunction "K_K") (pintype "passive"))
      (node (ref "R236") (pin "2") (pinfunction "2_2") (pintype "passive"))
    )
    (net (code "23") (name "Net-(D38-PadK)") (class "Default")
      (node (ref "D38") (pin "K") (pinfunction "K_K") (pintype "passive"))
      (node (ref "R237") (pin "2") (pinfunction "2_2") (pintype "passive"))
    )
    (net (code "24") (name "Net-(D39-PadK)") (class "Default")
      (node (ref "D39") (pin "K") (pinfunction "K_K") (pintype "passive"))
      (node (ref "R246") (pin "2") (pinfunction "2_2") (pintype "passive"))
    )
    (net (code "25") (name "Net-(D40-PadK)") (class "Default")
      (node (ref "D40") (pin "K") (pinfunction "K_K") (pintype "passive"))
      (node (ref "R248") (pin "2") (pinfunction "2_2") (pintype "passive"))
    )
    (net (code "26") (name "Net-(Q7-Pad1)") (class "Default")
      (node (ref "Q7") (pin "1") (pintype "passive"))
      (node (ref "R238") (pin "1") (pinfunction "1_1") (pintype "passive"))
    )
    (net (code "27") (name "Net-(Q7-Pad3)") (class "Default")
      (node (ref "Q7") (pin "3") (pintype "passive"))
      (node (ref "R230") (pin "1") (pinfunction "1_1") (pintype "passive"))
    )
    (net (code "28") (name "Net-(Q8-Pad1)") (class "Default")
      (node (ref "Q8") (pin "1") (pintype "passive"))
      (node (ref "R239") (pin "1") (pinfunction "1_1") (pintype "passive"))
    )
    (net (code "29") (name "Net-(Q8-Pad3)") (class "Default")
      (node (ref "Q8") (pin "3") (pintype "passive"))
      (node (ref "R231") (pin "1") (pinfunction "1_1") (pintype "passive"))
    )
    (net (code "30") (name "Net-(Q9-Pad1)") (class "Default")
      (node (ref "Q9") (pin "1") (pintype "passive"))
      (node (ref "R240") (pin "1") (pinfunction "1_1") (pintype "passive"))
    )
    (net (code "31") (name "Net-(Q9-Pad3)") (class "Default")
      (node (ref "Q9") (pin "3") (pintype "passive"))
      (node (ref "R232") (pin "1") (pinfunction "1_1") (pintype "passive"))
    )
    (net (code "32") (name "Net-(Q10-Pad1)") (class "Default")
      (node (ref "Q10") (pin "1") (pintype "passive"))
      (node (ref "R241") (pin "1") (pinfunction "1_1") (pintype "passive"))
    )
    (net (code "33") (name "Net-(Q10-Pad3)") (class "Default")
      (node (ref "Q10") (pin "3") (pintype "passive"))
      (node (ref "R233") (pin "1") (pinfunction "1_1") (pintype "passive"))
    )
    (net (code "34") (name "Net-(Q11-Pad1)") (class "Default")
      (node (ref "Q11") (pin "1") (pintype "passive"))
      (node (ref "R242") (pin "1") (pinfunction "1_1") (pintype "passive"))
    )
    (net (code "35") (name "Net-(Q11-Pad3)") (class "Default")
      (node (ref "Q11") (pin "3") (pintype "passive"))
      (node (ref "R234") (pin "1") (pinfunction "1_1") (pintype "passive"))
    )
    (net (code "36") (name "Net-(Q12-Pad1)") (class "Default")
      (node (ref "Q12") (pin "1") (pintype "passive"))
      (node (ref "R243") (pin "1") (pinfunction "1_1") (pintype "passive"))
    )
    (net (code "37") (name "Net-(Q12-Pad3)") (class "Default")
      (node (ref "Q12") (pin "3") (pintype "passive"))
      (node (ref "R235") (pin "1") (pinfunction "1_1") (pintype "passive"))
    )
    (net (code "38") (name "Net-(Q13-Pad1)") (class "Default")
      (node (ref "Q13") (pin "1") (pintype "passive"))
      (node (ref "R244") (pin "1") (pinfunction "1_1") (pintype "passive"))
    )
    (net (code "39") (name "Net-(Q13-Pad3)") (class "Default")
      (node (ref "Q13") (pin "3") (pintype "passive"))
      (node (ref "R236") (pin "1") (pinfunction "1_1") (pintype "passive"))
    )
    (net (code "40") (name "Net-(Q14-Pad1)") (class "Default")
      (node (ref "Q14") (pin "1") (pintype "passive"))
      (node (ref "R245") (pin "1") (pinfunction "1_1") (pintype "passive"))
    )
    (net (code "41") (name "Net-(Q14-Pad3)") (class "Default")
      (node (ref "Q14") (pin "3") (pintype "passive"))
      (node (ref "R237") (pin "1") (pinfunction "1_1") (pintype "passive"))
    )
    (net (code "42") (name "Net-(Q15-Pad1)") (class "Default")
      (node (ref "Q15") (pin "1") (pintype "passive"))
      (node (ref "R250") (pin "1") (pinfunction "1_1") (pintype "passive"))
    )
    (net (code "43") (name "Net-(Q15-Pad3)") (class "Default")
      (node (ref "Q15") (pin "3") (pintype "passive"))
      (node (ref "R246") (pin "1") (pinfunction "1_1") (pintype "passive"))
    )
    (net (code "44") (name "Net-(Q16-Pad1)") (class "Default")
      (node (ref "Q16") (pin "1") (pintype "passive"))
      (node (ref "R251") (pin "1") (pinfunction "1_1") (pintype "passive"))
    )
    (net (code "45") (name "Net-(Q16-Pad3)") (class "Default")
      (node (ref "Q16") (pin "3") (pintype "passive"))
      (node (ref "R248") (pin "1") (pinfunction "1_1") (pintype "passive"))
    )
    (net (code "46") (name "Net-(R247-Pad1)") (class "Default")
      (node (ref "R247") (pin "1") (pinfunction "1_1") (pintype "passive"))
      (node (ref "R250") (pin "2") (pinfunction "2_2") (pintype "passive"))
      (node (ref "R252") (pin "2") (pinfunction "2_2") (pintype "passive"))
    )
    (net (code "47") (name "Net-(R249-Pad1)") (class "Default")
      (node (ref "R249") (pin "1") (pinfunction "1_1") (pintype "passive"))
      (node (ref "R251") (pin "2") (pinfunction "2_2") (pintype "passive"))
      (node (ref "R253") (pin "2") (pinfunction "2_2") (pintype "passive"))
    )
    (net (code "48") (name "VTT") (class "Default")
      (node (ref "C172") (pin "2") (pinfunction "2_2") (pintype "passive"))
      (node (ref "C173") (pin "2") (pinfunction "2_2") (pintype "passive"))
      (node (ref "C174") (pin "2") (pinfunction "2_2") (pintype "passive"))
    )
  )
)
